# Sheet1.net
KiCad netlist of a schematic drawn in Altium Designer
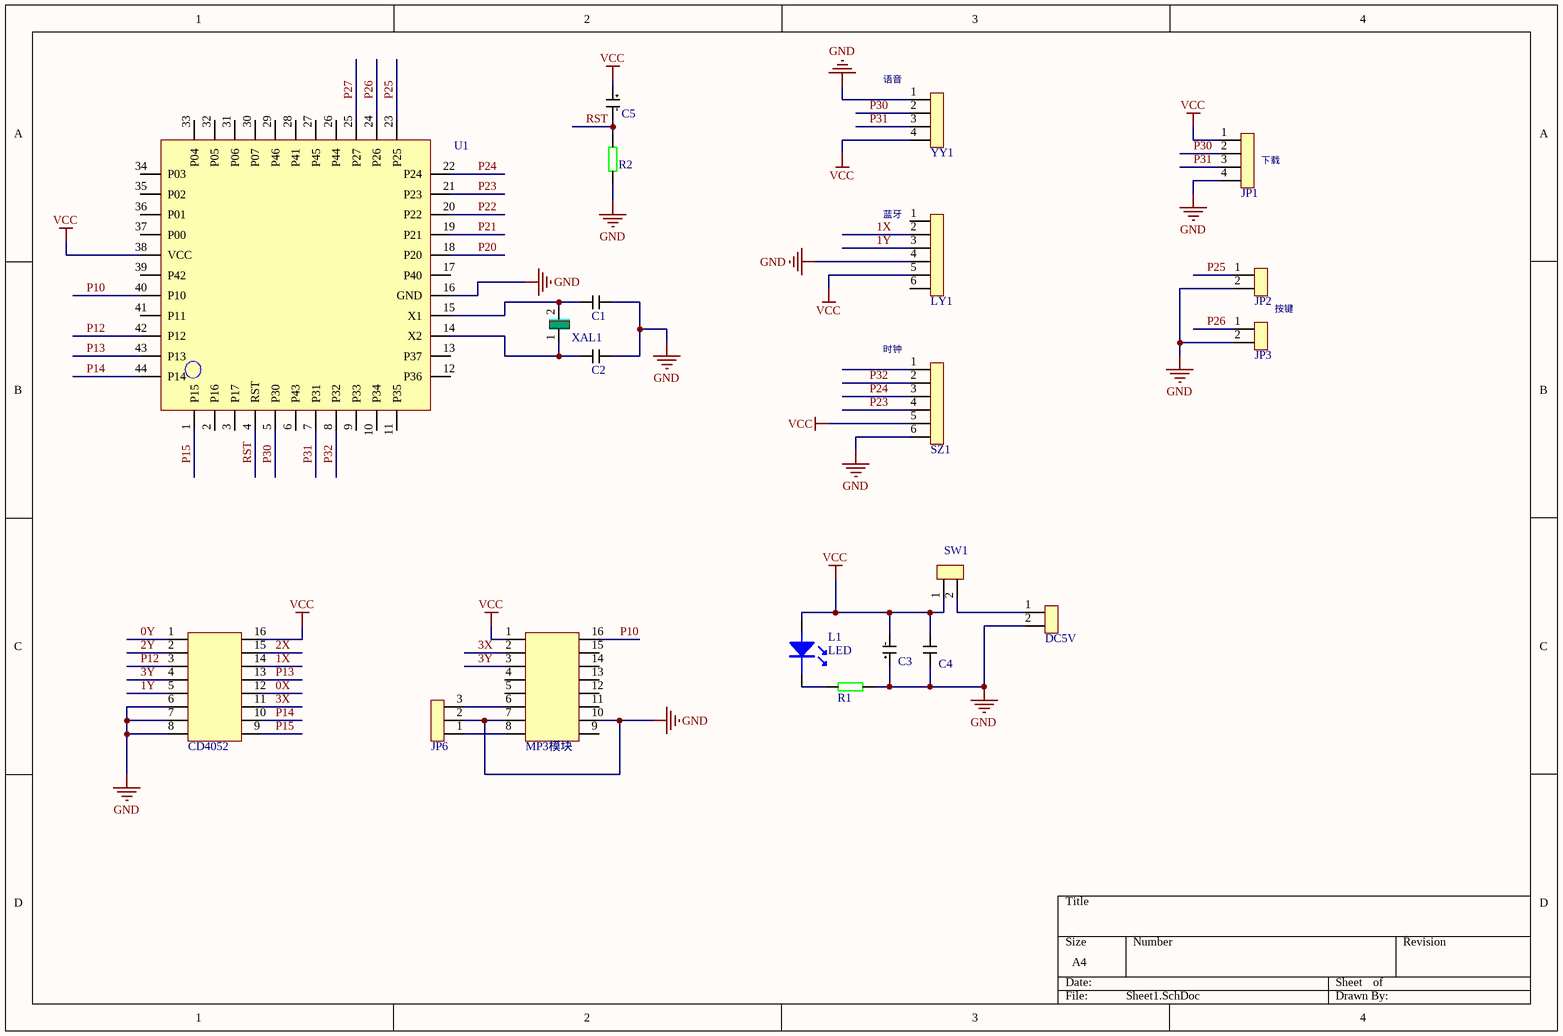
[diagram p0: Sheet1.SchDoc]

(export (version "E")
  (design (tool "Eeschema 10.0.6"))
  (components
    (comp (ref "C1") (value "CAP") (footprint "0805") (libsource (lib "集成库") (part "CAP")))
    (comp (ref "C2") (value "CAP") (footprint "0805") (libsource (lib "集成库") (part "CAP")))
    (comp (ref "C3") (value "CAP+") (footprint "CAP-100mil") (libsource (lib "集成库") (part "CAP+")))
    (comp (ref "C4") (value "CAP") (footprint "CAP-100mil") (libsource (lib "集成库") (part "CAP")))
    (comp (ref "C5") (value "CAP+") (footprint "CAP-100mil") (libsource (lib "集成库") (part "CAP+")))
    (comp (ref "DC5V") (value "SIP-2") (footprint "SIP-2") (libsource (lib "集成库") (part "SIP-2")))
    (comp (ref "JP1") (value "SIP-4") (footprint "SIP-4") (libsource (lib "集成库") (part "SIP-4")))
    (comp (ref "JP2") (value "SIP-2") (footprint "RES-200mil") (libsource (lib "集成库") (part "SIP-2")))
    (comp (ref "JP3") (value "SIP-2") (footprint "RES-200mil") (libsource (lib "集成库") (part "SIP-2")))
    (comp (ref "JP6") (value "SIP-3") (footprint "SIP-3") (libsource (lib "集成库") (part "SIP-3")))
    (comp (ref "L1") (value "LED") (footprint "LED") (libsource (lib "集成库") (part "LED")))
    (comp (ref "LY1") (value "SIP-6") (footprint "SIP-6") (libsource (lib "集成库") (part "SIP-6")))
    (comp (ref "R1") (value "RES") (footprint "RES-300mil") (libsource (lib "集成库") (part "RES")))
    (comp (ref "R2") (value "RES") (footprint "RES-300mil") (libsource (lib "集成库") (part "RES")))
    (comp (ref "SW1") (value "SIP-2") (footprint "RES-200mil") (libsource (lib "") (part "SIP-2_1")))
    (comp (ref "SZ1") (value "SIP-6") (footprint "SIP-6") (libsource (lib "集成库") (part "SIP-6")))
    (comp (ref "U1") (value "STC89C52RC") (footprint "LQFP-44") (libsource (lib "集成库") (part "STC89C52RC")))
    (comp (ref "U2") (value "CD4052") (footprint "SO-16") (libsource (lib "集成库") (part "DIP-16")))
    (comp (ref "U3") (value "MP3模块") (footprint "DIP-16-660mil") (libsource (lib "集成库") (part "DIP-16")))
    (comp (ref "XAL1") (value "晶振") (footprint "晶振-200mil") (libsource (lib "集成库") (part "晶振")))
    (comp (ref "YY1") (value "SIP-4") (footprint "SIP-4") (libsource (lib "集成库") (part "SIP-4")))
  )
  (nets
    (net (code "1") (name "/0X") (class "Default")
      (node (ref "U2") (pin "12") (pinfunction "12_12") (pintype "passive"))
    )
    (net (code "2") (name "/0Y") (class "Default")
      (node (ref "U2") (pin "1") (pinfunction "1_1") (pintype "passive"))
    )
    (net (code "3") (name "/1X") (class "Default")
      (node (ref "LY1") (pin "2") (pinfunction "2_2") (pintype "passive"))
      (node (ref "U2") (pin "14") (pinfunction "14_14") (pintype "passive"))
    )
    (net (code "4") (name "/1Y") (class "Default")
      (node (ref "LY1") (pin "3") (pinfunction "3_3") (pintype "passive"))
      (node (ref "U2") (pin "5") (pinfunction "5_5") (pintype "passive"))
    )
    (net (code "5") (name "/2X") (class "Default")
      (node (ref "U2") (pin "15") (pinfunction "15_15") (pintype "passive"))
    )
    (net (code "6") (name "/2Y") (class "Default")
      (node (ref "U2") (pin "2") (pinfunction "2_2") (pintype "passive"))
    )
    (net (code "7") (name "/3X") (class "Default")
      (node (ref "U2") (pin "11") (pinfunction "11_11") (pintype "passive"))
      (node (ref "U3") (pin "2") (pinfunction "2_2") (pintype "passive"))
    )
    (net (code "8") (name "/3Y") (class "Default")
      (node (ref "U2") (pin "4") (pinfunction "4_4") (pintype "passive"))
      (node (ref "U3") (pin "3") (pinfunction "3_3") (pintype "passive"))
    )
    (net (code "9") (name "/P10") (class "Default")
      (node (ref "U1") (pin "40") (pinfunction "P10_40") (pintype "passive"))
      (node (ref "U3") (pin "16") (pinfunction "16_16") (pintype "passive"))
    )
    (net (code "10") (name "/P12") (class "Default")
      (node (ref "U1") (pin "42") (pinfunction "P12_42") (pintype "passive"))
      (node (ref "U2") (pin "3") (pinfunction "3_3") (pintype "passive"))
    )
    (net (code "11") (name "/P13") (class "Default")
      (node (ref "U1") (pin "43") (pinfunction "P13_43") (pintype "passive"))
      (node (ref "U2") (pin "13") (pinfunction "13_13") (pintype "passive"))
    )
    (net (code "12") (name "/P14") (class "Default")
      (node (ref "U1") (pin "44") (pinfunction "P14_44") (pintype "passive"))
      (node (ref "U2") (pin "10") (pinfunction "10_10") (pintype "passive"))
    )
    (net (code "13") (name "/P15") (class "Default")
      (node (ref "U1") (pin "1") (pinfunction "P15_1") (pintype "passive"))
      (node (ref "U2") (pin "9") (pinfunction "9_9") (pintype "passive"))
    )
    (net (code "14") (name "/P20") (class "Default")
      (node (ref "U1") (pin "18") (pinfunction "P20_18") (pintype "passive"))
    )
    (net (code "15") (name "/P21") (class "Default")
      (node (ref "U1") (pin "19") (pinfunction "P21_19") (pintype "passive"))
    )
    (net (code "16") (name "/P22") (class "Default")
      (node (ref "U1") (pin "20") (pinfunction "P22_20") (pintype "passive"))
    )
    (net (code "17") (name "/P23") (class "Default")
      (node (ref "SZ1") (pin "4") (pinfunction "4_4") (pintype "passive"))
      (node (ref "U1") (pin "21") (pinfunction "P23_21") (pintype "passive"))
    )
    (net (code "18") (name "/P24") (class "Default")
      (node (ref "SZ1") (pin "3") (pinfunction "3_3") (pintype "passive"))
      (node (ref "U1") (pin "22") (pinfunction "P24_22") (pintype "passive"))
    )
    (net (code "19") (name "/P25") (class "Default")
      (node (ref "JP2") (pin "1") (pinfunction "1_1") (pintype "passive"))
      (node (ref "U1") (pin "23") (pinfunction "P25_23") (pintype "passive"))
    )
    (net (code "20") (name "/P26") (class "Default")
      (node (ref "JP3") (pin "1") (pinfunction "1_1") (pintype "passive"))
      (node (ref "U1") (pin "24") (pinfunction "P26_24") (pintype "passive"))
    )
    (net (code "21") (name "/P27") (class "Default")
      (node (ref "U1") (pin "25") (pinfunction "P27_25") (pintype "passive"))
    )
    (net (code "22") (name "/P30") (class "Default")
      (node (ref "JP1") (pin "2") (pinfunction "2_2") (pintype "passive"))
      (node (ref "U1") (pin "5") (pinfunction "P30_5") (pintype "passive"))
      (node (ref "YY1") (pin "2") (pinfunction "2_2") (pintype "passive"))
    )
    (net (code "23") (name "/P31") (class "Default")
      (node (ref "JP1") (pin "3") (pinfunction "3_3") (pintype "passive"))
      (node (ref "U1") (pin "7") (pinfunction "P31_7") (pintype "passive"))
      (node (ref "YY1") (pin "3") (pinfunction "3_3") (pintype "passive"))
    )
    (net (code "24") (name "/P32") (class "Default")
      (node (ref "SZ1") (pin "2") (pinfunction "2_2") (pintype "passive"))
      (node (ref "U1") (pin "8") (pinfunction "P32_8") (pintype "passive"))
    )
    (net (code "25") (name "/RST") (class "Default")
      (node (ref "C5") (pin "2") (pinfunction "2_2") (pintype "passive"))
      (node (ref "R2") (pin "1") (pinfunction "1_1") (pintype "passive"))
      (node (ref "U1") (pin "4") (pinfunction "RST_4") (pintype "passive"))
    )
    (net (code "26") (name "GND") (class "Default")
      (node (ref "C1") (pin "2") (pinfunction "2_2") (pintype "passive"))
      (node (ref "C2") (pin "2") (pinfunction "2_2") (pintype "passive"))
      (node (ref "C3") (pin "1") (pinfunction "1_1") (pintype "passive"))
      (node (ref "C4") (pin "2") (pinfunction "2_2") (pintype "passive"))
      (node (ref "DC5V") (pin "2") (pinfunction "2_2") (pintype "passive"))
      (node (ref "JP1") (pin "4") (pinfunction "4_4") (pintype "passive"))
      (node (ref "JP2") (pin "2") (pinfunction "2_2") (pintype "passive"))
      (node (ref "JP3") (pin "2") (pinfunction "2_2") (pintype "passive"))
      (node (ref "JP6") (pin "2") (pinfunction "2_2") (pintype "passive"))
      (node (ref "LY1") (pin "4") (pinfunction "4_4") (pintype "passive"))
      (node (ref "R1") (pin "2") (pinfunction "2_2") (pintype "passive"))
      (node (ref "R2") (pin "2") (pinfunction "2_2") (pintype "passive"))
      (node (ref "SZ1") (pin "6") (pinfunction "6_6") (pintype "passive"))
      (node (ref "U1") (pin "16") (pinfunction "GND_16") (pintype "passive"))
      (node (ref "U2") (pin "6") (pinfunction "6_6") (pintype "passive"))
      (node (ref "U2") (pin "7") (pinfunction "7_7") (pintype "passive"))
      (node (ref "U2") (pin "8") (pinfunction "8_8") (pintype "passive"))
      (node (ref "U3") (pin "10") (pinfunction "10_10") (pintype "passive"))
      (node (ref "U3") (pin "7") (pinfunction "7_7") (pintype "passive"))
      (node (ref "YY1") (pin "1") (pinfunction "1_1") (pintype "passive"))
    )
    (net (code "27") (name "Net-(DC5V-Pad1)") (class "Default")
      (node (ref "DC5V") (pin "1") (pinfunction "1_1") (pintype "passive"))
      (node (ref "SW1") (pin "2") (pinfunction "2_2") (pintype "passive"))
    )
    (net (code "28") (name "Net-(JP6-Pad1)") (class "Default")
      (node (ref "JP6") (pin "1") (pinfunction "1_1") (pintype "passive"))
      (node (ref "U3") (pin "8") (pinfunction "8_8") (pintype "passive"))
    )
    (net (code "29") (name "Net-(JP6-Pad3)") (class "Default")
      (node (ref "JP6") (pin "3") (pinfunction "3_3") (pintype "passive"))
      (node (ref "U3") (pin "6") (pinfunction "6_6") (pintype "passive"))
    )
    (net (code "30") (name "Net-(L1-Pad2)") (class "Default")
      (node (ref "L1") (pin "2") (pinfunction "2_2") (pintype "passive"))
      (node (ref "R1") (pin "1") (pinfunction "1_1") (pintype "passive"))
    )
    (net (code "31") (name "Net-(U1-X1)") (class "Default")
      (node (ref "C1") (pin "1") (pinfunction "1_1") (pintype "passive"))
      (node (ref "U1") (pin "15") (pinfunction "X1_15") (pintype "passive"))
      (node (ref "XAL1") (pin "2") (pinfunction "2_2") (pintype "passive"))
    )
    (net (code "32") (name "Net-(U1-X2)") (class "Default")
      (node (ref "C2") (pin "1") (pinfunction "1_1") (pintype "passive"))
      (node (ref "U1") (pin "14") (pinfunction "X2_14") (pintype "passive"))
      (node (ref "XAL1") (pin "1") (pinfunction "1_1") (pintype "passive"))
    )
    (net (code "33") (name "VCC") (class "Default")
      (node (ref "C3") (pin "2") (pinfunction "2_2") (pintype "passive"))
      (node (ref "C4") (pin "1") (pinfunction "1_1") (pintype "passive"))
      (node (ref "C5") (pin "1") (pinfunction "1_1") (pintype "passive"))
      (node (ref "JP1") (pin "1") (pinfunction "1_1") (pintype "passive"))
      (node (ref "L1") (pin "1") (pinfunction "1_1") (pintype "passive"))
      (node (ref "LY1") (pin "5") (pinfunction "5_5") (pintype "passive"))
      (node (ref "SW1") (pin "1") (pinfunction "1_1") (pintype "passive"))
      (node (ref "SZ1") (pin "5") (pinfunction "5_5") (pintype "passive"))
      (node (ref "U1") (pin "38") (pinfunction "VCC_38") (pintype "passive"))
      (node (ref "U2") (pin "16") (pinfunction "16_16") (pintype "passive"))
      (node (ref "U3") (pin "1") (pinfunction "1_1") (pintype "passive"))
      (node (ref "YY1") (pin "4") (pinfunction "4_4") (pintype "passive"))
    )
    (net (code "34") (name "unconnected-(LY1-Pad1)") (class "Default")
      (node (ref "LY1") (pin "1") (pinfunction "1_1") (pintype "passive"))
    )
    (net (code "35") (name "unconnected-(LY1-Pad6)") (class "Default")
      (node (ref "LY1") (pin "6") (pinfunction "6_6") (pintype "passive"))
    )
    (net (code "36") (name "unconnected-(SZ1-Pad1)") (class "Default")
      (node (ref "SZ1") (pin "1") (pinfunction "1_1") (pintype "passive"))
    )
    (net (code "37") (name "unconnected-(U1-P00-Pad37)") (class "Default")
      (node (ref "U1") (pin "37") (pinfunction "P00_37") (pintype "passive"))
    )
    (net (code "38") (name "unconnected-(U1-P01-Pad36)") (class "Default")
      (node (ref "U1") (pin "36") (pinfunction "P01_36") (pintype "passive"))
    )
    (net (code "39") (name "unconnected-(U1-P02-Pad35)") (class "Default")
      (node (ref "U1") (pin "35") (pinfunction "P02_35") (pintype "passive"))
    )
    (net (code "40") (name "unconnected-(U1-P03-Pad34)") (class "Default")
      (node (ref "U1") (pin "34") (pinfunction "P03_34") (pintype "passive"))
    )
    (net (code "41") (name "unconnected-(U1-P04-Pad33)") (class "Default")
      (node (ref "U1") (pin "33") (pinfunction "P04_33") (pintype "passive"))
    )
    (net (code "42") (name "unconnected-(U1-P05-Pad32)") (class "Default")
      (node (ref "U1") (pin "32") (pinfunction "P05_32") (pintype "passive"))
    )
    (net (code "43") (name "unconnected-(U1-P06-Pad31)") (class "Default")
      (node (ref "U1") (pin "31") (pinfunction "P06_31") (pintype "passive"))
    )
    (net (code "44") (name "unconnected-(U1-P07-Pad30)") (class "Default")
      (node (ref "U1") (pin "30") (pinfunction "P07_30") (pintype "passive"))
    )
    (net (code "45") (name "unconnected-(U1-P11-Pad41)") (class "Default")
      (node (ref "U1") (pin "41") (pinfunction "P11_41") (pintype "passive"))
    )
    (net (code "46") (name "unconnected-(U1-P16-Pad2)") (class "Default")
      (node (ref "U1") (pin "2") (pinfunction "P16_2") (pintype "passive"))
    )
    (net (code "47") (name "unconnected-(U1-P17-Pad3)") (class "Default")
      (node (ref "U1") (pin "3") (pinfunction "P17_3") (pintype "passive"))
    )
    (net (code "48") (name "unconnected-(U1-P33-Pad9)") (class "Default")
      (node (ref "U1") (pin "9") (pinfunction "P33_9") (pintype "passive"))
    )
    (net (code "49") (name "unconnected-(U1-P34-Pad10)") (class "Default")
      (node (ref "U1") (pin "10") (pinfunction "P34_10") (pintype "passive"))
    )
    (net (code "50") (name "unconnected-(U1-P35-Pad11)") (class "Default")
      (node (ref "U1") (pin "11") (pinfunction "P35_11") (pintype "passive"))
    )
    (net (code "51") (name "unconnected-(U1-P36-Pad12)") (class "Default")
      (node (ref "U1") (pin "12") (pinfunction "P36_12") (pintype "passive"))
    )
    (net (code "52") (name "unconnected-(U1-P37-Pad13)") (class "Default")
      (node (ref "U1") (pin "13") (pinfunction "P37_13") (pintype "passive"))
    )
    (net (code "53") (name "unconnected-(U1-P40-Pad17)") (class "Default")
      (node (ref "U1") (pin "17") (pinfunction "P40_17") (pintype "passive"))
    )
    (net (code "54") (name "unconnected-(U1-P41-Pad28)") (class "Default")
      (node (ref "U1") (pin "28") (pinfunction "P41_28") (pintype "passive"))
    )
    (net (code "55") (name "unconnected-(U1-P42-Pad39)") (class "Default")
      (node (ref "U1") (pin "39") (pinfunction "P42_39") (pintype "passive"))
    )
    (net (code "56") (name "unconnected-(U1-P43-Pad6)") (class "Default")
      (node (ref "U1") (pin "6") (pinfunction "P43_6") (pintype "passive"))
    )
    (net (code "57") (name "unconnected-(U1-P44-Pad26)") (class "Default")
      (node (ref "U1") (pin "26") (pinfunction "P44_26") (pintype "passive"))
    )
    (net (code "58") (name "unconnected-(U1-P45-Pad27)") (class "Default")
      (node (ref "U1") (pin "27") (pinfunction "P45_27") (pintype "passive"))
    )
    (net (code "59") (name "unconnected-(U1-P46-Pad29)") (class "Default")
      (node (ref "U1") (pin "29") (pinfunction "P46_29") (pintype "passive"))
    )
    (net (code "60") (name "unconnected-(U3-Pad4)") (class "Default")
      (node (ref "U3") (pin "4") (pinfunction "4_4") (pintype "passive"))
    )
    (net (code "61") (name "unconnected-(U3-Pad5)") (class "Default")
      (node (ref "U3") (pin "5") (pinfunction "5_5") (pintype "passive"))
    )
    (net (code "62") (name "unconnected-(U3-Pad9)") (class "Default")
      (node (ref "U3") (pin "9") (pinfunction "9_9") (pintype "passive"))
    )
    (net (code "63") (name "unconnected-(U3-Pad11)") (class "Default")
      (node (ref "U3") (pin "11") (pinfunction "11_11") (pintype "passive"))
    )
    (net (code "64") (name "unconnected-(U3-Pad12)") (class "Default")
      (node (ref "U3") (pin "12") (pinfunction "12_12") (pintype "passive"))
    )
    (net (code "65") (name "unconnected-(U3-Pad13)") (class "Default")
      (node (ref "U3") (pin "13") (pinfunction "13_13") (pintype "passive"))
    )
    (net (code "66") (name "unconnected-(U3-Pad14)") (class "Default")
      (node (ref "U3") (pin "14") (pinfunction "14_14") (pintype "passive"))
    )
    (net (code "67") (name "unconnected-(U3-Pad15)") (class "Default")
      (node (ref "U3") (pin "15") (pinfunction "15_15") (pintype "passive"))
    )
  )
)
